# RasPiDV.net
KiCad netlist of a schematic drawn in EAGLE
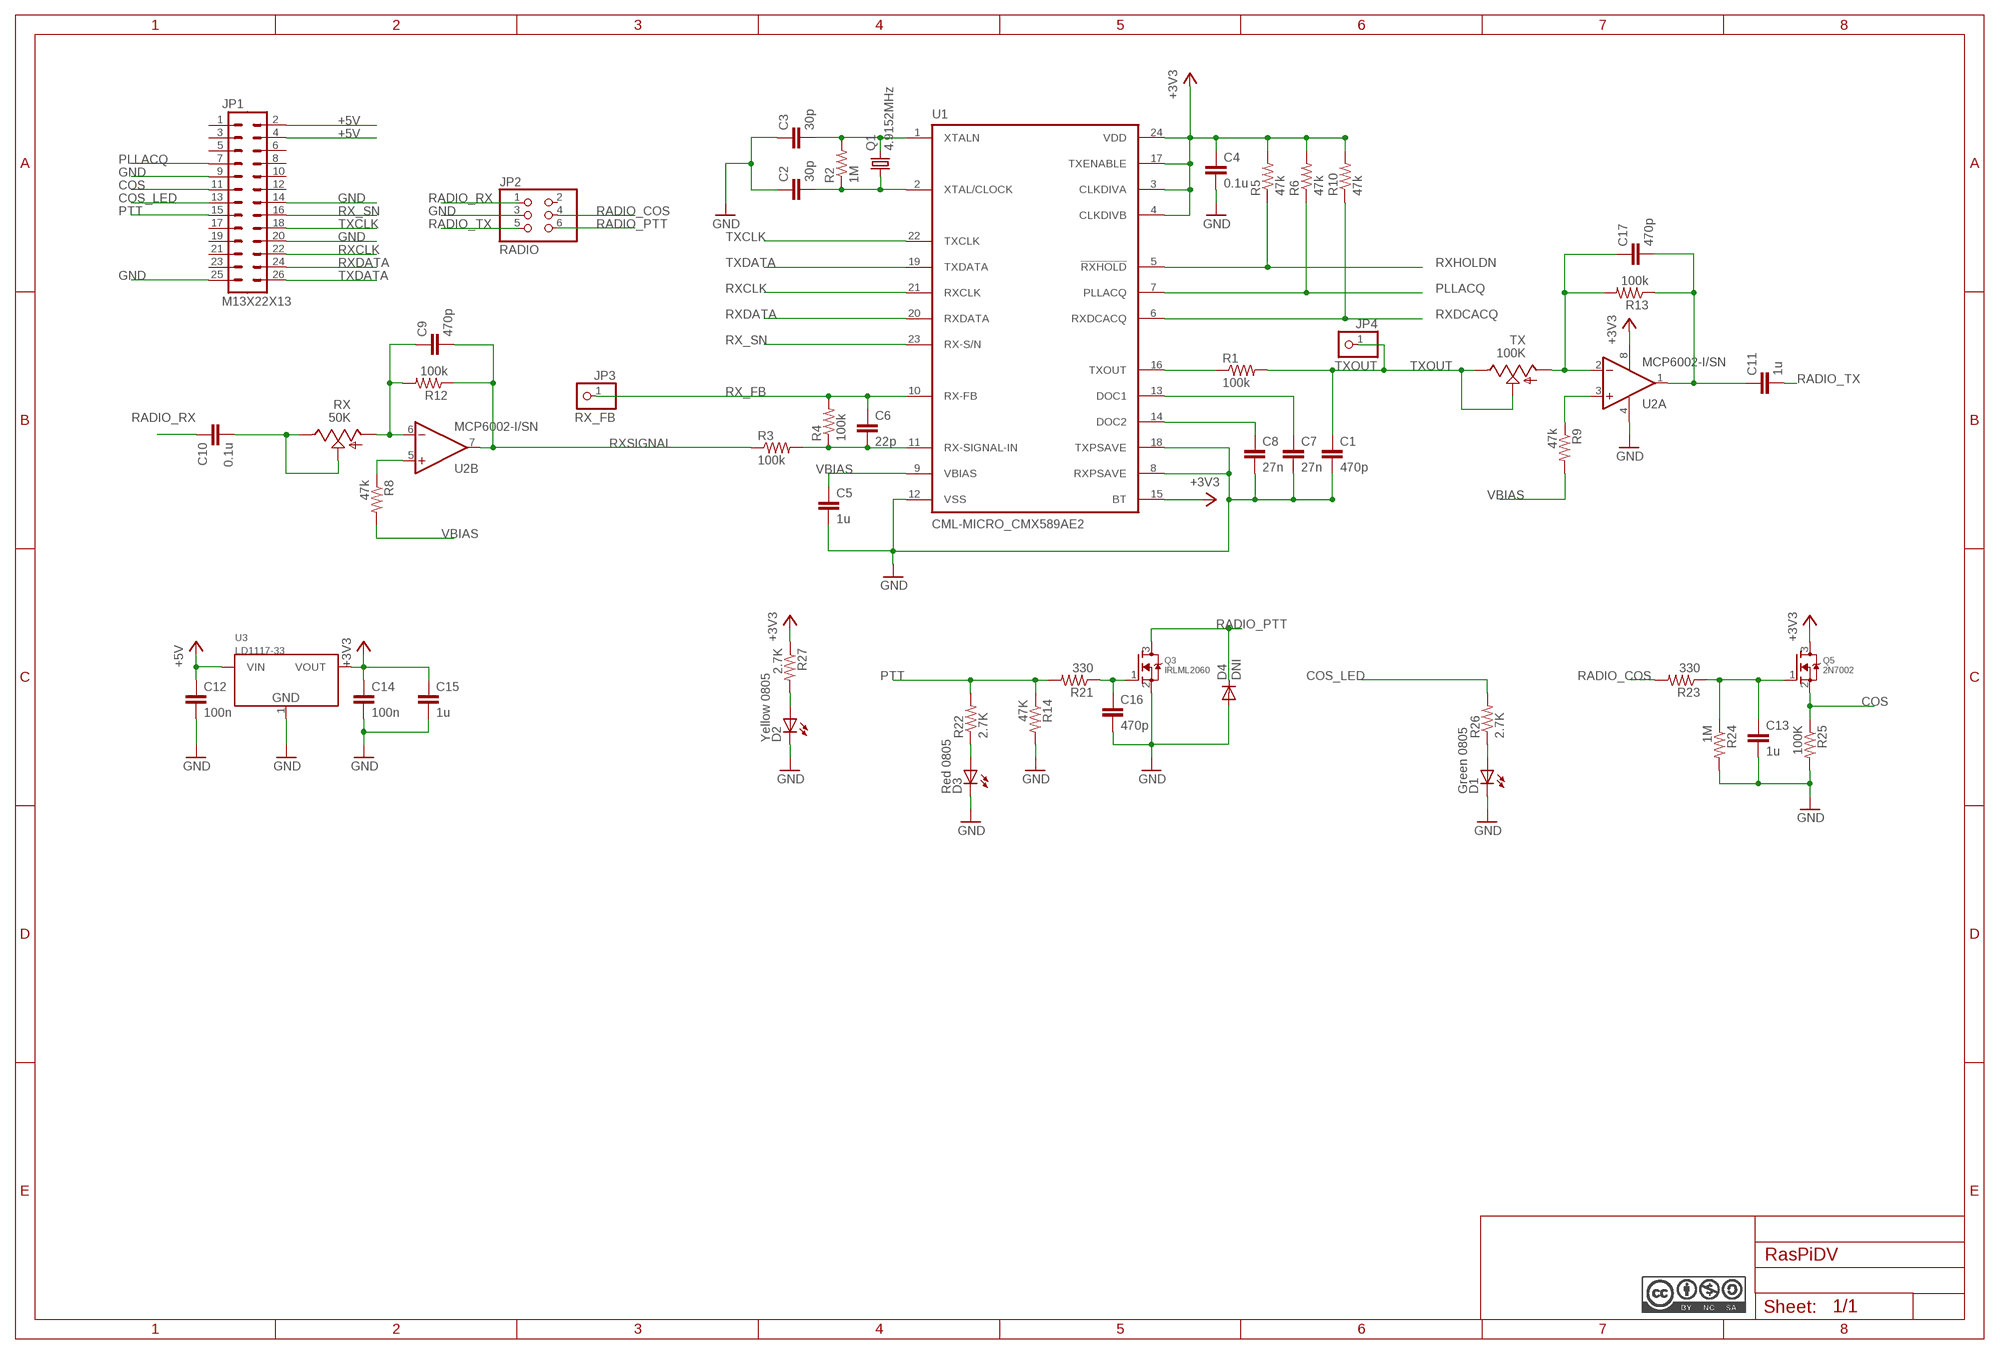
[diagram p0: schematic, sheet 1]

(export (version "E")
  (design (tool "Eeschema 10.0.6"))
  (components
    (comp (ref "C1")
      (value "470p")
      (footprint "eagle-import:C0805")
      (libsource (lib "eagle-import") (part "C-EUC0805"))
    )
    (comp (ref "C2")
      (value "30p")
      (footprint "eagle-import:C0805")
      (libsource (lib "eagle-import") (part "C-EUC0805"))
    )
    (comp (ref "C3")
      (value "30p")
      (footprint "eagle-import:C0805")
      (libsource (lib "eagle-import") (part "C-EUC0805"))
    )
    (comp (ref "C4")
      (value "0.1u")
      (footprint "eagle-import:C0805")
      (libsource (lib "eagle-import") (part "C-EUC0805"))
    )
    (comp (ref "C5")
      (value "1u")
      (footprint "eagle-import:C0805")
      (libsource (lib "eagle-import") (part "C-EUC0805"))
    )
    (comp (ref "C6")
      (value "22p")
      (footprint "eagle-import:C0805")
      (libsource (lib "eagle-import") (part "C-EUC0805"))
    )
    (comp (ref "C7")
      (value "27n")
      (footprint "eagle-import:C0805")
      (libsource (lib "eagle-import") (part "C-EUC0805"))
    )
    (comp (ref "C8")
      (value "27n")
      (footprint "eagle-import:C0805")
      (libsource (lib "eagle-import") (part "C-EUC0805"))
    )
    (comp (ref "C9")
      (value "470p")
      (footprint "eagle-import:C0805")
      (libsource (lib "eagle-import") (part "C-EUC0805"))
    )
    (comp (ref "C10")
      (value "0.1u")
      (footprint "eagle-import:C0805")
      (libsource (lib "eagle-import") (part "C-EUC0805"))
    )
    (comp (ref "C11")
      (value "1u")
      (footprint "eagle-import:C0805")
      (libsource (lib "eagle-import") (part "C-EUC0805"))
    )
    (comp (ref "C12")
      (value "100n")
      (footprint "eagle-import:C0805")
      (libsource (lib "eagle-import") (part "C-EUC0805"))
    )
    (comp (ref "C13")
      (value "1u")
      (footprint "eagle-import:C0805")
      (libsource (lib "eagle-import") (part "C-EUC0805"))
    )
    (comp (ref "C14")
      (value "100n")
      (footprint "eagle-import:C0805")
      (libsource (lib "eagle-import") (part "C-EUC0805"))
    )
    (comp (ref "C15")
      (value "1u")
      (footprint "eagle-import:C0805")
      (libsource (lib "eagle-import") (part "C-EUC0805"))
    )
    (comp (ref "C16")
      (value "470p")
      (footprint "eagle-import:C0805")
      (libsource (lib "eagle-import") (part "C-EUC0805"))
    )
    (comp (ref "C17")
      (value "470p")
      (footprint "eagle-import:C0805")
      (libsource (lib "eagle-import") (part "C-EUC0805"))
    )
    (comp (ref "D1")
      (value "Green 0805")
      (footprint "eagle-import:CHIPLED_0805")
      (libsource (lib "eagle-import") (part "LEDCHIPLED_0805"))
    )
    (comp (ref "D2")
      (value "Yellow 0805")
      (footprint "eagle-import:CHIPLED_0805")
      (libsource (lib "eagle-import") (part "LEDCHIPLED_0805"))
    )
    (comp (ref "D3")
      (value "Red 0805")
      (footprint "eagle-import:CHIPLED_0805")
      (libsource (lib "eagle-import") (part "LEDCHIPLED_0805"))
    )
    (comp (ref "D4")
      (value "DNI")
      (footprint "eagle-import:MICROMELF-R")
      (libsource (lib "eagle-import") (part "DIODE-MICROMELF-R"))
    )
    (comp (ref "JP1")
      (value "M13X22X13")
      (footprint "eagle-import:2X13")
      (libsource (lib "eagle-import") (part "M13X22X13"))
    )
    (comp (ref "JP2")
      (value "RADIO")
      (footprint "eagle-import:2X03_ROUND_70MIL")
      (libsource (lib "eagle-import") (part "HEADER-2X3"))
    )
    (comp (ref "JP3")
      (value "RX_FB")
      (footprint "eagle-import:1X01_ROUND")
      (libsource (lib "eagle-import") (part "HEADER-1X1ROUND"))
    )
    (comp (ref "JP4")
      (value "TXOUT")
      (footprint "eagle-import:1X01_ROUND")
      (libsource (lib "eagle-import") (part "HEADER-1X1ROUND"))
    )
    (comp (ref "Q1")
      (value "4.9152MHz")
      (footprint "eagle-import:CRYSTAL_HC49_S")
      (libsource (lib "eagle-import") (part "CRYSTAL_CRYSTALHC49S"))
    )
    (comp (ref "Q3")
      (value "IRLML2060")
      (footprint "eagle-import:SOT23")
      (libsource (lib "eagle-import") (part "MOSFET-NREFLOW"))
    )
    (comp (ref "Q5")
      (value "2N7002")
      (footprint "eagle-import:SOT23-R")
      (libsource (lib "eagle-import") (part "microbuilder_MOSFET-NREFLOW"))
    )
    (comp (ref "R1")
      (value "100k")
      (footprint "eagle-import:R0805W")
      (libsource (lib "eagle-import") (part "R-US_R0805W"))
    )
    (comp (ref "R2")
      (value "1M")
      (footprint "eagle-import:R0805W")
      (libsource (lib "eagle-import") (part "R-US_R0805W"))
    )
    (comp (ref "R3")
      (value "100k")
      (footprint "eagle-import:R0805W")
      (libsource (lib "eagle-import") (part "R-US_R0805W"))
    )
    (comp (ref "R4")
      (value "100k")
      (footprint "eagle-import:R0805W")
      (libsource (lib "eagle-import") (part "R-US_R0805W"))
    )
    (comp (ref "R5")
      (value "47k")
      (footprint "eagle-import:R0805W")
      (libsource (lib "eagle-import") (part "R-US_R0805W"))
    )
    (comp (ref "R6")
      (value "47k")
      (footprint "eagle-import:R0805W")
      (libsource (lib "eagle-import") (part "R-US_R0805W"))
    )
    (comp (ref "R8")
      (value "47k")
      (footprint "eagle-import:R0805W")
      (libsource (lib "eagle-import") (part "R-US_R0805W"))
    )
    (comp (ref "R9")
      (value "47k")
      (footprint "eagle-import:R0805W")
      (libsource (lib "eagle-import") (part "R-US_R0805W"))
    )
    (comp (ref "R10")
      (value "47k")
      (footprint "eagle-import:R0805W")
      (libsource (lib "eagle-import") (part "R-US_R0805W"))
    )
    (comp (ref "R12")
      (value "100k")
      (footprint "eagle-import:R0805W")
      (libsource (lib "eagle-import") (part "R-US_R0805W"))
    )
    (comp (ref "R13")
      (value "100k")
      (footprint "eagle-import:R0805W")
      (libsource (lib "eagle-import") (part "R-US_R0805W"))
    )
    (comp (ref "R14")
      (value "47K")
      (footprint "eagle-import:R0805W")
      (libsource (lib "eagle-import") (part "R-US_R0805W"))
    )
    (comp (ref "R21")
      (value "330")
      (footprint "eagle-import:R0805W")
      (libsource (lib "eagle-import") (part "R-US_R0805W"))
    )
    (comp (ref "R22")
      (value "2.7K")
      (footprint "eagle-import:R0805W")
      (libsource (lib "eagle-import") (part "R-US_R0805W"))
    )
    (comp (ref "R23")
      (value "330")
      (footprint "eagle-import:R0805W")
      (libsource (lib "eagle-import") (part "R-US_R0805W"))
    )
    (comp (ref "R24")
      (value "1M")
      (footprint "eagle-import:R0805W")
      (libsource (lib "eagle-import") (part "R-US_R0805W"))
    )
    (comp (ref "R25")
      (value "100K")
      (footprint "eagle-import:R0805W")
      (libsource (lib "eagle-import") (part "R-US_R0805W"))
    )
    (comp (ref "R26")
      (value "2.7K")
      (footprint "eagle-import:R0805W")
      (libsource (lib "eagle-import") (part "R-US_R0805W"))
    )
    (comp (ref "R27")
      (value "2.7K")
      (footprint "eagle-import:R0805W")
      (libsource (lib "eagle-import") (part "R-US_R0805W"))
    )
    (comp (ref "RX")
      (value "50K")
      (footprint "eagle-import:B25P")
      (libsource (lib "eagle-import") (part "TRIM_US-B25P"))
    )
    (comp (ref "TX")
      (value "100K")
      (footprint "eagle-import:B25P")
      (libsource (lib "eagle-import") (part "TRIM_US-B25P"))
    )
    (comp (ref "U1")
      (value "CML-MICRO_CMX589AE2")
      (footprint "eagle-import:AIS_MK2_CML-MICRO_TSSOP24")
      (libsource (lib "eagle-import") (part "AIS_MK2_CML-MICRO_CMX589AE2"))
    )
    (comp (ref "U2")
      (value "MCP6002-I/SN")
      (footprint "eagle-import:SOIC-8")
      (libsource (lib "eagle-import") (part "MCP6002-I/SN"))
    )
    (comp (ref "U3")
      (value "LD1117-33")
      (footprint "eagle-import:SOT223")
      (libsource (lib "eagle-import") (part "LD1117-3.3SOT223"))
    )
  )
  (nets
    (net (code "1") (name "+3V3") (class "Default")
      (node (ref "C14") (pin "1") (pinfunction "1_1") (pintype "passive"))
      (node (ref "C15") (pin "1") (pinfunction "1_1") (pintype "passive"))
      (node (ref "C4") (pin "1") (pinfunction "1_1") (pintype "passive"))
      (node (ref "Q5") (pin "3") (pinfunction "D_3") (pintype "bidirectional"))
      (node (ref "R10") (pin "2") (pinfunction "2_2") (pintype "passive"))
      (node (ref "R27") (pin "1") (pinfunction "1_1") (pintype "passive"))
      (node (ref "R5") (pin "2") (pinfunction "2_2") (pintype "passive"))
      (node (ref "R6") (pin "2") (pinfunction "2_2") (pintype "passive"))
      (node (ref "U1") (pin "15") (pinfunction "BT_15") (pintype "input"))
      (node (ref "U1") (pin "17") (pinfunction "TXENABLE_17") (pintype "input"))
      (node (ref "U1") (pin "24") (pinfunction "VDD_24") (pintype "power_in"))
      (node (ref "U1") (pin "3") (pinfunction "CLKDIVA_3") (pintype "input"))
      (node (ref "U1") (pin "4") (pinfunction "CLKDIVB_4") (pintype "input"))
      (node (ref "U2") (pin "8") (pinfunction "V+_8") (pintype "power_in"))
      (node (ref "U3") (pin "2") (pinfunction "VOUT_2") (pintype "bidirectional"))
    )
    (net (code "2") (name "+5V") (class "Default")
      (node (ref "C12") (pin "1") (pinfunction "1_1") (pintype "passive"))
      (node (ref "JP1") (pin "2") (pinfunction "2_2") (pintype "passive"))
      (node (ref "JP1") (pin "4") (pinfunction "4_4") (pintype "passive"))
      (node (ref "U3") (pin "3") (pinfunction "VIN_3") (pintype "bidirectional"))
    )
    (net (code "3") (name "/COS") (class "Default")
      (node (ref "JP1") (pin "11") (pinfunction "11_11") (pintype "passive"))
      (node (ref "Q5") (pin "2") (pinfunction "S_2") (pintype "bidirectional"))
      (node (ref "R25") (pin "1") (pinfunction "1_1") (pintype "passive"))
    )
    (net (code "4") (name "/COS_LED") (class "Default")
      (node (ref "JP1") (pin "13") (pinfunction "13_13") (pintype "passive"))
      (node (ref "R26") (pin "2") (pinfunction "2_2") (pintype "passive"))
    )
    (net (code "5") (name "/PLLACQ") (class "Default")
      (node (ref "JP1") (pin "7") (pinfunction "7_7") (pintype "passive"))
      (node (ref "R6") (pin "1") (pinfunction "1_1") (pintype "passive"))
      (node (ref "U1") (pin "7") (pinfunction "PLLACQ_7") (pintype "input"))
    )
    (net (code "6") (name "/PTT") (class "Default")
      (node (ref "JP1") (pin "15") (pinfunction "15_15") (pintype "passive"))
      (node (ref "R14") (pin "1") (pinfunction "1_1") (pintype "passive"))
      (node (ref "R21") (pin "2") (pinfunction "2_2") (pintype "passive"))
      (node (ref "R22") (pin "2") (pinfunction "2_2") (pintype "passive"))
    )
    (net (code "7") (name "/RADIO_COS") (class "Default")
      (node (ref "JP2") (pin "4") (pinfunction "4_4") (pintype "passive"))
      (node (ref "R23") (pin "2") (pinfunction "2_2") (pintype "passive"))
    )
    (net (code "8") (name "/RADIO_PTT") (class "Default")
      (node (ref "D4") (pin "C") (pinfunction "C_C") (pintype "passive"))
      (node (ref "JP2") (pin "6") (pinfunction "6_6") (pintype "passive"))
      (node (ref "Q3") (pin "3") (pinfunction "D_3") (pintype "bidirectional"))
    )
    (net (code "9") (name "/RADIO_RX") (class "Default")
      (node (ref "C10") (pin "1") (pinfunction "1_1") (pintype "passive"))
      (node (ref "JP2") (pin "1") (pinfunction "1_1") (pintype "passive"))
    )
    (net (code "10") (name "/RADIO_TX") (class "Default")
      (node (ref "C11") (pin "2") (pinfunction "2_2") (pintype "passive"))
      (node (ref "JP2") (pin "5") (pinfunction "5_5") (pintype "passive"))
    )
    (net (code "11") (name "/RXCLK") (class "Default")
      (node (ref "JP1") (pin "22") (pinfunction "22_22") (pintype "passive"))
      (node (ref "U1") (pin "21") (pinfunction "RXCLK_21") (pintype "output"))
    )
    (net (code "12") (name "/RXDATA") (class "Default")
      (node (ref "JP1") (pin "24") (pinfunction "24_24") (pintype "passive"))
      (node (ref "U1") (pin "20") (pinfunction "RXDATA_20") (pintype "output"))
    )
    (net (code "13") (name "/RXDCACQ") (class "Default")
      (node (ref "R10") (pin "1") (pinfunction "1_1") (pintype "passive"))
      (node (ref "U1") (pin "6") (pinfunction "RXDCACQ_6") (pintype "input"))
    )
    (net (code "14") (name "/RXHOLDN") (class "Default")
      (node (ref "R5") (pin "1") (pinfunction "1_1") (pintype "passive"))
      (node (ref "U1") (pin "5") (pinfunction "~{RXHOLD}_5") (pintype "input"))
    )
    (net (code "15") (name "/RXSIGNAL") (class "Default")
      (node (ref "C9") (pin "2") (pinfunction "2_2") (pintype "passive"))
      (node (ref "R12") (pin "1") (pinfunction "1_1") (pintype "passive"))
      (node (ref "R3") (pin "1") (pinfunction "1_1") (pintype "passive"))
      (node (ref "U2") (pin "7") (pinfunction "OUT_7") (pintype "output"))
    )
    (net (code "16") (name "/RX_FB") (class "Default")
      (node (ref "C6") (pin "1") (pinfunction "1_1") (pintype "passive"))
      (node (ref "JP3") (pin "1") (pinfunction "1_1") (pintype "passive"))
      (node (ref "R4") (pin "2") (pinfunction "2_2") (pintype "passive"))
      (node (ref "U1") (pin "10") (pinfunction "RX-FB_10") (pintype "input"))
    )
    (net (code "17") (name "/RX_SN") (class "Default")
      (node (ref "JP1") (pin "16") (pinfunction "16_16") (pintype "passive"))
      (node (ref "U1") (pin "23") (pinfunction "RX-S/N_23") (pintype "output"))
    )
    (net (code "18") (name "/TXCLK") (class "Default")
      (node (ref "JP1") (pin "18") (pinfunction "18_18") (pintype "passive"))
      (node (ref "U1") (pin "22") (pinfunction "TXCLK_22") (pintype "output"))
    )
    (net (code "19") (name "/TXDATA") (class "Default")
      (node (ref "JP1") (pin "26") (pinfunction "26_26") (pintype "passive"))
      (node (ref "U1") (pin "19") (pinfunction "TXDATA_19") (pintype "input"))
    )
    (net (code "20") (name "/TXOUT") (class "Default")
      (node (ref "C1") (pin "1") (pinfunction "1_1") (pintype "passive"))
      (node (ref "JP4") (pin "1") (pinfunction "1_1") (pintype "passive"))
      (node (ref "R1") (pin "2") (pinfunction "2_2") (pintype "passive"))
      (node (ref "TX") (pin "E") (pinfunction "E_E") (pintype "passive"))
      (node (ref "TX") (pin "S") (pinfunction "S_S") (pintype "passive"))
    )
    (net (code "21") (name "/VBIAS") (class "Default")
      (node (ref "C5") (pin "1") (pinfunction "1_1") (pintype "passive"))
      (node (ref "R8") (pin "2") (pinfunction "2_2") (pintype "passive"))
      (node (ref "R9") (pin "2") (pinfunction "2_2") (pintype "passive"))
      (node (ref "U1") (pin "9") (pinfunction "VBIAS_9") (pintype "input"))
    )
    (net (code "22") (name "GND") (class "Default")
      (node (ref "C1") (pin "2") (pinfunction "2_2") (pintype "passive"))
      (node (ref "C12") (pin "2") (pinfunction "2_2") (pintype "passive"))
      (node (ref "C13") (pin "2") (pinfunction "2_2") (pintype "passive"))
      (node (ref "C14") (pin "2") (pinfunction "2_2") (pintype "passive"))
      (node (ref "C15") (pin "2") (pinfunction "2_2") (pintype "passive"))
      (node (ref "C16") (pin "2") (pinfunction "2_2") (pintype "passive"))
      (node (ref "C2") (pin "1") (pinfunction "1_1") (pintype "passive"))
      (node (ref "C3") (pin "1") (pinfunction "1_1") (pintype "passive"))
      (node (ref "C4") (pin "2") (pinfunction "2_2") (pintype "passive"))
      (node (ref "C5") (pin "2") (pinfunction "2_2") (pintype "passive"))
      (node (ref "C7") (pin "2") (pinfunction "2_2") (pintype "passive"))
      (node (ref "C8") (pin "2") (pinfunction "2_2") (pintype "passive"))
      (node (ref "D1") (pin "C") (pinfunction "C_C") (pintype "passive"))
      (node (ref "D2") (pin "C") (pinfunction "C_C") (pintype "passive"))
      (node (ref "D3") (pin "C") (pinfunction "C_C") (pintype "passive"))
      (node (ref "D4") (pin "A") (pinfunction "A_A") (pintype "passive"))
      (node (ref "JP1") (pin "14") (pinfunction "14_14") (pintype "passive"))
      (node (ref "JP1") (pin "20") (pinfunction "20_20") (pintype "passive"))
      (node (ref "JP1") (pin "25") (pinfunction "25_25") (pintype "passive"))
      (node (ref "JP1") (pin "9") (pinfunction "9_9") (pintype "passive"))
      (node (ref "JP2") (pin "3") (pinfunction "3_3") (pintype "passive"))
      (node (ref "Q3") (pin "2") (pinfunction "S_2") (pintype "bidirectional"))
      (node (ref "R14") (pin "2") (pinfunction "2_2") (pintype "passive"))
      (node (ref "R24") (pin "2") (pinfunction "2_2") (pintype "passive"))
      (node (ref "R25") (pin "2") (pinfunction "2_2") (pintype "passive"))
      (node (ref "U1") (pin "12") (pinfunction "VSS_12") (pintype "power_in"))
      (node (ref "U1") (pin "18") (pinfunction "TXPSAVE_18") (pintype "input"))
      (node (ref "U1") (pin "8") (pinfunction "RXPSAVE_8") (pintype "input"))
      (node (ref "U2") (pin "4") (pinfunction "V-_4") (pintype "power_in"))
      (node (ref "U3") (pin "1") (pinfunction "GND_1") (pintype "bidirectional"))
    )
    (net (code "23") (name "Net-(C10-Pad2)") (class "Default")
      (node (ref "C10") (pin "2") (pinfunction "2_2") (pintype "passive"))
      (node (ref "RX") (pin "E") (pinfunction "E_E") (pintype "passive"))
      (node (ref "RX") (pin "S") (pinfunction "S_S") (pintype "passive"))
    )
    (net (code "24") (name "Net-(D1-PadA)") (class "Default")
      (node (ref "D1") (pin "A") (pinfunction "A_A") (pintype "passive"))
      (node (ref "R26") (pin "1") (pinfunction "1_1") (pintype "passive"))
    )
    (net (code "25") (name "Net-(D2-PadA)") (class "Default")
      (node (ref "D2") (pin "A") (pinfunction "A_A") (pintype "passive"))
      (node (ref "R27") (pin "2") (pinfunction "2_2") (pintype "passive"))
    )
    (net (code "26") (name "Net-(D3-PadA)") (class "Default")
      (node (ref "D3") (pin "A") (pinfunction "A_A") (pintype "passive"))
      (node (ref "R22") (pin "1") (pinfunction "1_1") (pintype "passive"))
    )
    (net (code "27") (name "Net-(Q3-G)") (class "Default")
      (node (ref "C16") (pin "1") (pinfunction "1_1") (pintype "passive"))
      (node (ref "Q3") (pin "1") (pinfunction "G_1") (pintype "bidirectional"))
      (node (ref "R21") (pin "1") (pinfunction "1_1") (pintype "passive"))
    )
    (net (code "28") (name "Net-(Q5-G)") (class "Default")
      (node (ref "C13") (pin "1") (pinfunction "1_1") (pintype "passive"))
      (node (ref "Q5") (pin "1") (pinfunction "G_1") (pintype "bidirectional"))
      (node (ref "R23") (pin "1") (pinfunction "1_1") (pintype "passive"))
      (node (ref "R24") (pin "1") (pinfunction "1_1") (pintype "passive"))
    )
    (net (code "29") (name "Net-(U1-DOC1)") (class "Default")
      (node (ref "C7") (pin "1") (pinfunction "1_1") (pintype "passive"))
      (node (ref "U1") (pin "13") (pinfunction "DOC1_13") (pintype "passive"))
    )
    (net (code "30") (name "Net-(U1-DOC2)") (class "Default")
      (node (ref "C8") (pin "1") (pinfunction "1_1") (pintype "passive"))
      (node (ref "U1") (pin "14") (pinfunction "DOC2_14") (pintype "passive"))
    )
    (net (code "31") (name "Net-(U1-RX-SIGNAL-IN)") (class "Default")
      (node (ref "C6") (pin "2") (pinfunction "2_2") (pintype "passive"))
      (node (ref "R3") (pin "2") (pinfunction "2_2") (pintype "passive"))
      (node (ref "R4") (pin "1") (pinfunction "1_1") (pintype "passive"))
      (node (ref "U1") (pin "11") (pinfunction "RX-SIGNAL-IN_11") (pintype "input"))
    )
    (net (code "32") (name "Net-(U1-TXOUT)") (class "Default")
      (node (ref "R1") (pin "1") (pinfunction "1_1") (pintype "passive"))
      (node (ref "U1") (pin "16") (pinfunction "TXOUT_16") (pintype "output"))
    )
    (net (code "33") (name "Net-(U1-XTALN)") (class "Default")
      (node (ref "C3") (pin "2") (pinfunction "2_2") (pintype "passive"))
      (node (ref "Q1") (pin "2") (pinfunction "2_2") (pintype "passive"))
      (node (ref "R2") (pin "2") (pinfunction "2_2") (pintype "passive"))
      (node (ref "U1") (pin "1") (pinfunction "XTALN_1") (pintype "output"))
    )
    (net (code "34") (name "Net-(U1-XTAL{slash}CLOCK)") (class "Default")
      (node (ref "C2") (pin "2") (pinfunction "2_2") (pintype "passive"))
      (node (ref "Q1") (pin "1") (pinfunction "1_1") (pintype "passive"))
      (node (ref "R2") (pin "1") (pinfunction "1_1") (pintype "passive"))
      (node (ref "U1") (pin "2") (pinfunction "XTAL/CLOCK_2") (pintype "input"))
    )
    (net (code "35") (name "Net-(U2A-IN+)") (class "Default")
      (node (ref "R9") (pin "1") (pinfunction "1_1") (pintype "passive"))
      (node (ref "U2") (pin "3") (pinfunction "IN+_3") (pintype "input"))
    )
    (net (code "36") (name "Net-(U2A-IN-)") (class "Default")
      (node (ref "C17") (pin "1") (pinfunction "1_1") (pintype "passive"))
      (node (ref "R13") (pin "2") (pinfunction "2_2") (pintype "passive"))
      (node (ref "TX") (pin "A") (pinfunction "A_A") (pintype "passive"))
      (node (ref "U2") (pin "2") (pinfunction "IN-_2") (pintype "input"))
    )
    (net (code "37") (name "Net-(U2A-OUT)") (class "Default")
      (node (ref "C11") (pin "1") (pinfunction "1_1") (pintype "passive"))
      (node (ref "C17") (pin "2") (pinfunction "2_2") (pintype "passive"))
      (node (ref "R13") (pin "1") (pinfunction "1_1") (pintype "passive"))
      (node (ref "U2") (pin "1") (pinfunction "OUT_1") (pintype "output"))
    )
    (net (code "38") (name "Net-(U2B-IN+)") (class "Default")
      (node (ref "R8") (pin "1") (pinfunction "1_1") (pintype "passive"))
      (node (ref "U2") (pin "5") (pinfunction "IN+_5") (pintype "input"))
    )
    (net (code "39") (name "Net-(U2B-IN-)") (class "Default")
      (node (ref "C9") (pin "1") (pinfunction "1_1") (pintype "passive"))
      (node (ref "R12") (pin "2") (pinfunction "2_2") (pintype "passive"))
      (node (ref "RX") (pin "A") (pinfunction "A_A") (pintype "passive"))
      (node (ref "U2") (pin "6") (pinfunction "IN-_6") (pintype "input"))
    )
    (net (code "40") (name "unconnected-(JP1-Pad1)") (class "Default")
      (node (ref "JP1") (pin "1") (pinfunction "1_1") (pintype "passive"))
    )
    (net (code "41") (name "unconnected-(JP1-Pad3)") (class "Default")
      (node (ref "JP1") (pin "3") (pinfunction "3_3") (pintype "passive"))
    )
    (net (code "42") (name "unconnected-(JP1-Pad5)") (class "Default")
      (node (ref "JP1") (pin "5") (pinfunction "5_5") (pintype "passive"))
    )
    (net (code "43") (name "unconnected-(JP1-Pad6)") (class "Default")
      (node (ref "JP1") (pin "6") (pinfunction "6_6") (pintype "passive"))
    )
    (net (code "44") (name "unconnected-(JP1-Pad8)") (class "Default")
      (node (ref "JP1") (pin "8") (pinfunction "8_8") (pintype "passive"))
    )
    (net (code "45") (name "unconnected-(JP1-Pad10)") (class "Default")
      (node (ref "JP1") (pin "10") (pinfunction "10_10") (pintype "passive"))
    )
    (net (code "46") (name "unconnected-(JP1-Pad12)") (class "Default")
      (node (ref "JP1") (pin "12") (pinfunction "12_12") (pintype "passive"))
    )
    (net (code "47") (name "unconnected-(JP1-Pad17)") (class "Default")
      (node (ref "JP1") (pin "17") (pinfunction "17_17") (pintype "passive"))
    )
    (net (code "48") (name "unconnected-(JP1-Pad19)") (class "Default")
      (node (ref "JP1") (pin "19") (pinfunction "19_19") (pintype "passive"))
    )
    (net (code "49") (name "unconnected-(JP1-Pad21)") (class "Default")
      (node (ref "JP1") (pin "21") (pinfunction "21_21") (pintype "passive"))
    )
    (net (code "50") (name "unconnected-(JP1-Pad23)") (class "Default")
      (node (ref "JP1") (pin "23") (pinfunction "23_23") (pintype "passive"))
    )
    (net (code "51") (name "unconnected-(JP2-Pad2)") (class "Default")
      (node (ref "JP2") (pin "2") (pinfunction "2_2") (pintype "passive"))
    )
  )
)
